# RocketometerPx_9150.net
KiCad netlist of a schematic drawn in EAGLE
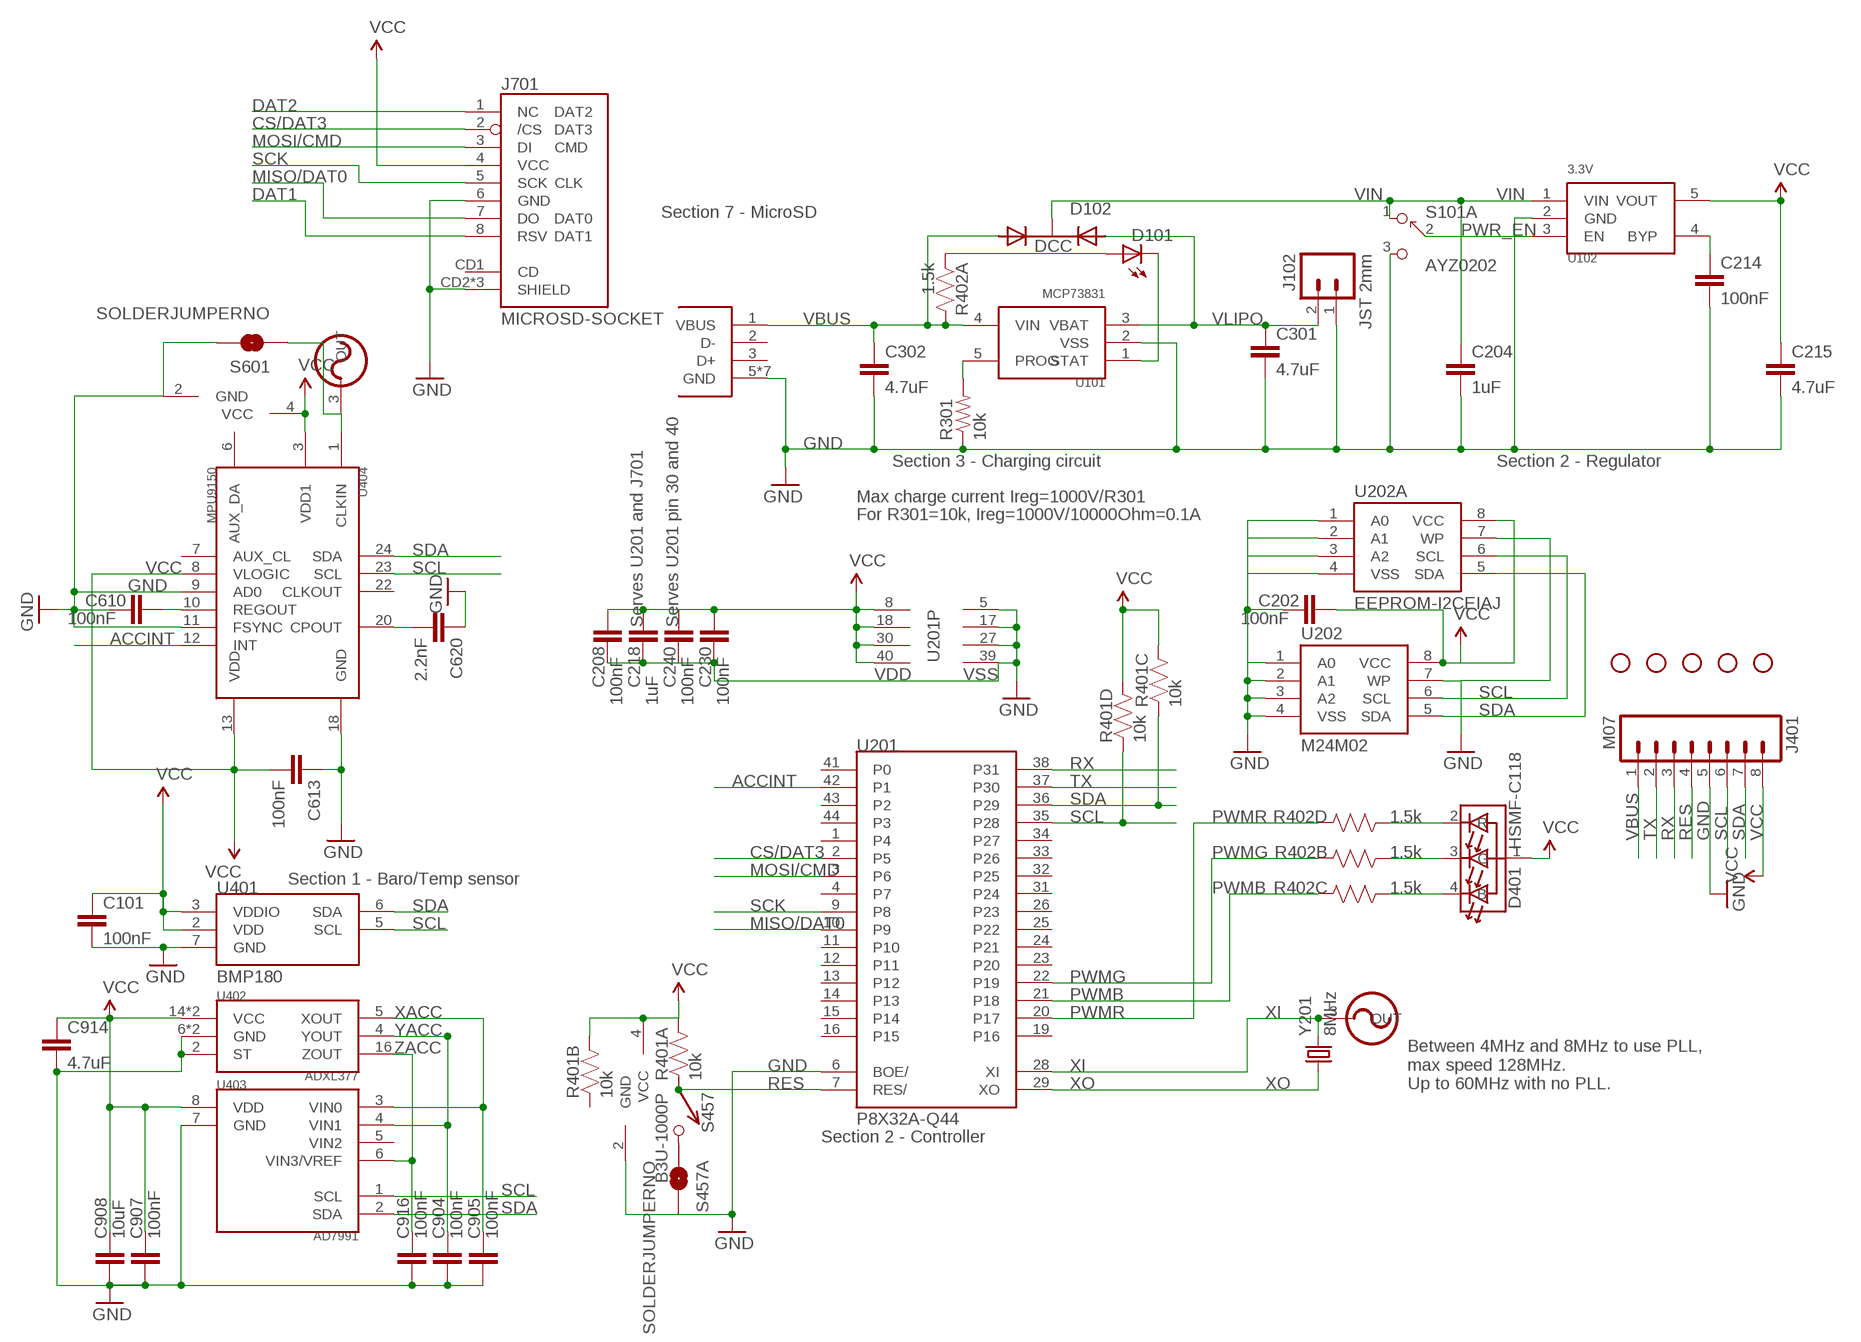
[diagram p0: schematic, sheet 1]

(export (version "E")
  (design (tool "Eeschema 10.0.6"))
  (components
    (comp (ref "C101")
      (value "100nF")
      (footprint "eagle-import:0402-CAP")
      (libsource (lib "eagle-import") (part "CAP0402-CAP"))
    )
    (comp (ref "C202")
      (value "100nF")
      (footprint "eagle-import:0402-CAP")
      (libsource (lib "eagle-import") (part "CAP0402-CAP"))
    )
    (comp (ref "C204")
      (value "1uF")
      (footprint "eagle-import:0402-CAP")
      (libsource (lib "eagle-import") (part "CAP0402-CAP"))
    )
    (comp (ref "C208")
      (value "100nF")
      (footprint "eagle-import:0402-CAP")
      (libsource (lib "eagle-import") (part "CAP0402-CAP"))
    )
    (comp (ref "C214")
      (value "100nF")
      (footprint "eagle-import:0402-CAP")
      (libsource (lib "eagle-import") (part "CAP0402-CAP"))
    )
    (comp (ref "C215")
      (value "4.7uF")
      (footprint "eagle-import:0402-CAP")
      (libsource (lib "eagle-import") (part "CAP0402-CAP"))
    )
    (comp (ref "C218")
      (value "1uF")
      (footprint "eagle-import:0402-CAP")
      (libsource (lib "eagle-import") (part "CAP0402-CAP"))
    )
    (comp (ref "C230")
      (value "100nF")
      (footprint "eagle-import:0402-CAP")
      (libsource (lib "eagle-import") (part "CAP0402-CAP"))
    )
    (comp (ref "C240")
      (value "100nF")
      (footprint "eagle-import:0402-CAP")
      (libsource (lib "eagle-import") (part "CAP0402-CAP"))
    )
    (comp (ref "C301")
      (value "4.7uF")
      (footprint "eagle-import:0402-CAP")
      (libsource (lib "eagle-import") (part "CAP0402-CAP"))
    )
    (comp (ref "C302")
      (value "4.7uF")
      (footprint "eagle-import:0402-CAP")
      (libsource (lib "eagle-import") (part "CAP0402-CAP"))
    )
    (comp (ref "C610")
      (value "100nF")
      (footprint "eagle-import:0402-CAP")
      (libsource (lib "eagle-import") (part "CAP0402-CAP"))
    )
    (comp (ref "C613")
      (value "100nF")
      (footprint "eagle-import:0402-CAP")
      (libsource (lib "eagle-import") (part "CAP0402-CAP"))
    )
    (comp (ref "C620")
      (value "2.2nF")
      (footprint "eagle-import:0402-CAP")
      (libsource (lib "eagle-import") (part "CAP0402-CAP"))
    )
    (comp (ref "C904")
      (value "100nF")
      (footprint "eagle-import:0402-CAP")
      (libsource (lib "eagle-import") (part "CAP0402-CAP"))
    )
    (comp (ref "C905")
      (value "100nF")
      (footprint "eagle-import:0402-CAP")
      (libsource (lib "eagle-import") (part "CAP0402-CAP"))
    )
    (comp (ref "C907")
      (value "100nF")
      (footprint "eagle-import:0402-CAP")
      (libsource (lib "eagle-import") (part "SparkFun-Passives_CAP0402-CAP"))
    )
    (comp (ref "C908")
      (value "10uF")
      (footprint "eagle-import:0603-CAP")
      (libsource (lib "eagle-import") (part "CAP0603-CAP"))
    )
    (comp (ref "C914")
      (value "4.7uF")
      (footprint "eagle-import:0402-CAP")
      (libsource (lib "eagle-import") (part "CAP0402-CAP"))
    )
    (comp (ref "C916")
      (value "100nF")
      (footprint "eagle-import:0402-CAP")
      (libsource (lib "eagle-import") (part "CAP0402-CAP"))
    )
    (comp (ref "D101")
      (value "YELLOW")
      (footprint "eagle-import:LED-0603")
      (libsource (lib "eagle-import") (part "LED0603"))
    )
    (comp (ref "D102")
      (value "DCC")
      (footprint "eagle-import:SOT-23-3")
      (libsource (lib "eagle-import") (part "PMEG2005CT"))
    )
    (comp (ref "D401")
      (value "HSMF-C118")
      (footprint "eagle-import:HSMF-C118")
      (libsource (lib "eagle-import") (part "HSMF-C118"))
    )
    (comp (ref "J101")
      (value "USB_MICROB_JSTGCT")
      (footprint "eagle-import:USB_MICROB_3075")
      (libsource (lib "eagle-import") (part "USB_MICROB_JSTGCT"))
    )
    (comp (ref "J102")
      (value "JST 2mm")
      (footprint "eagle-import:JST-2-SMD")
      (libsource (lib "eagle-import") (part "M02-JST-2MM-SMT"))
    )
    (comp (ref "J401")
      (value "M07")
      (footprint "eagle-import:1X08")
      (libsource (lib "eagle-import") (part "M081X08"))
    )
    (comp (ref "J701")
      (value "MICROSD-SOCKET")
      (footprint "eagle-import:MICROSD-SOCKET-PP")
      (libsource (lib "eagle-import") (part "MICROSD-SOCKET"))
    )
    (comp (ref "JP1")
      (value "STAND-OFFTIGHT")
      (footprint "eagle-import:STAND-OFF-TIGHT")
      (libsource (lib "eagle-import") (part "STAND-OFFTIGHT"))
    )
    (comp (ref "JP2")
      (value "STAND-OFFTIGHT")
      (footprint "eagle-import:STAND-OFF-TIGHT")
      (libsource (lib "eagle-import") (part "STAND-OFFTIGHT"))
    )
    (comp (ref "JP3")
      (value "STAND-OFFTIGHT")
      (footprint "eagle-import:STAND-OFF-TIGHT")
      (libsource (lib "eagle-import") (part "STAND-OFFTIGHT"))
    )
    (comp (ref "JP4")
      (value "STAND-OFFTIGHT")
      (footprint "eagle-import:STAND-OFF-TIGHT")
      (libsource (lib "eagle-import") (part "STAND-OFFTIGHT"))
    )
    (comp (ref "JP5")
      (value "STAND-OFFTIGHT")
      (footprint "eagle-import:STAND-OFF-TIGHT")
      (libsource (lib "eagle-import") (part "STAND-OFFTIGHT"))
    )
    (comp (ref "R301")
      (value "10k")
      (footprint "eagle-import:0402-RES")
      (libsource (lib "eagle-import") (part "RESISTOR0402-RES"))
    )
    (comp (ref "R401")
      (value "10k")
      (footprint "eagle-import:CRA04")
      (fields (field (name "DIGIKEY") "CRA4S810KCT-ND"))
      (libsource (lib "eagle-import") (part "RP404"))
    )
    (comp (ref "R402")
      (value "1.5k")
      (footprint "eagle-import:CRA04")
      (fields (field (name "DIGIKEY") "CRA4S81.5KCT-ND"))
      (libsource (lib "eagle-import") (part "RP404"))
    )
    (comp (ref "S101")
      (value "AYZ0202")
      (footprint "eagle-import:AYZ0202")
      (libsource (lib "eagle-import") (part "AYZ0202"))
    )
    (comp (ref "S457")
      (value "B3U-1000P")
      (footprint "eagle-import:B3U-1000P")
      (libsource (lib "eagle-import") (part "B3U-1000P"))
    )
    (comp (ref "S457A")
      (value "SOLDERJUMPERNO")
      (footprint "eagle-import:SJ_2S-NO")
      (libsource (lib "eagle-import") (part "SOLDERJUMPERNO"))
    )
    (comp (ref "S601")
      (value "SOLDERJUMPERNO")
      (footprint "eagle-import:SJ_2S-NO")
      (libsource (lib "eagle-import") (part "SOLDERJUMPERNO"))
    )
    (comp (ref "U101")
      (value "MCP73831")
      (footprint "eagle-import:SOT-23-5")
      (libsource (lib "eagle-import") (part "MCP73831"))
    )
    (comp (ref "U102")
      (value "3.3V")
      (footprint "eagle-import:SOT-23-5")
      (libsource (lib "eagle-import") (part "MIC5319D5"))
    )
    (comp (ref "U201")
      (value "P8X32A-Q44")
      (footprint "eagle-import:P8X32A-Q44")
      (fields (field (name "DIGIKEY") "P8X32A-Q44-ND"))
      (libsource (lib "eagle-import") (part "P8X32A-Q44"))
    )
    (comp (ref "U202")
      (value "M24M02")
      (footprint "eagle-import:SO8N")
      (libsource (lib "eagle-import") (part "EEPROM-I2C"))
    )
    (comp (ref "U202A")
      (value "EEPROM-I2CEIAJ")
      (footprint "eagle-import:SO08-EIAJ")
      (libsource (lib "eagle-import") (part "EEPROM-I2CEIAJ"))
    )
    (comp (ref "U401")
      (value "BMP180")
      (footprint "eagle-import:BMP180")
      (libsource (lib "eagle-import") (part "BMP180"))
    )
    (comp (ref "U402")
      (value "ADXL377")
      (footprint "eagle-import:ADXL377")
      (libsource (lib "eagle-import") (part "ADXL377"))
    )
    (comp (ref "U403")
      (value "AD7991")
      (footprint "eagle-import:SOT-23-8")
      (libsource (lib "eagle-import") (part "AD799X"))
    )
    (comp (ref "U404")
      (value "MPU9150")
      (footprint "eagle-import:MPU60X0")
      (libsource (lib "eagle-import") (part "MPU6050"))
    )
    (comp (ref "Y201")
      (value "8MHz")
      (footprint "eagle-import:CRYSTAL_SMD_3_2MM_2_5MM")
      (libsource (lib "eagle-import") (part "NX3225GD"))
    )
    (comp (ref "Y202")
      (value "8MHz")
      (footprint "eagle-import:CRYSTAL_SMD_5MM_3_2MM")
      (libsource (lib "eagle-import") (part "EM53T"))
    )
    (comp (ref "Y401")
      (value "19.2MHz")
      (footprint "eagle-import:CRYSTAL_SMD_5MM_3_2MM")
      (libsource (lib "eagle-import") (part "EM53T"))
    )
  )
  (nets
    (net (code "1") (name "/ACCINT") (class "Default")
      (node (ref "U201") (pin "42") (pinfunction "P1_42") (pintype "bidirectional"))
      (node (ref "U404") (pin "12") (pinfunction "INT_12") (pintype "output"))
    )
    (net (code "2") (name "/CS{slash}DAT3") (class "Default")
      (node (ref "J701") (pin "2") (pinfunction "/CS_2") (pintype "bidirectional"))
      (node (ref "U201") (pin "2") (pinfunction "P5_2") (pintype "bidirectional"))
    )
    (net (code "3") (name "/DAT1") (class "Default")
      (node (ref "J701") (pin "8") (pinfunction "RSV_8") (pintype "bidirectional"))
    )
    (net (code "4") (name "/DAT2") (class "Default")
      (node (ref "J701") (pin "1") (pinfunction "NC_1") (pintype "bidirectional"))
    )
    (net (code "5") (name "/MISO{slash}DAT0") (class "Default")
      (node (ref "J701") (pin "7") (pinfunction "DO_7") (pintype "bidirectional"))
      (node (ref "U201") (pin "10") (pinfunction "P9_10") (pintype "bidirectional"))
    )
    (net (code "6") (name "/MOSI{slash}CMD") (class "Default")
      (node (ref "J701") (pin "3") (pinfunction "DI_3") (pintype "bidirectional"))
      (node (ref "U201") (pin "3") (pinfunction "P6_3") (pintype "bidirectional"))
    )
    (net (code "7") (name "/PWMB") (class "Default")
      (node (ref "R402") (pin "6") (pinfunction "2_6") (pintype "passive"))
      (node (ref "U201") (pin "21") (pinfunction "P18_21") (pintype "bidirectional"))
    )
    (net (code "8") (name "/PWMG") (class "Default")
      (node (ref "R402") (pin "7") (pinfunction "2_7") (pintype "passive"))
      (node (ref "U201") (pin "22") (pinfunction "P19_22") (pintype "bidirectional"))
    )
    (net (code "9") (name "/PWMR") (class "Default")
      (node (ref "R402") (pin "5") (pinfunction "2_5") (pintype "passive"))
      (node (ref "U201") (pin "20") (pinfunction "P17_20") (pintype "bidirectional"))
    )
    (net (code "10") (name "/PWR_EN") (class "Default")
      (node (ref "S101") (pin "2") (pinfunction "P$3_2") (pintype "bidirectional"))
      (node (ref "U102") (pin "3") (pinfunction "EN_3") (pintype "bidirectional"))
    )
    (net (code "11") (name "/RES") (class "Default")
      (node (ref "J401") (pin "4") (pinfunction "4_4") (pintype "passive"))
      (node (ref "R401") (pin "1") (pinfunction "1_1") (pintype "passive"))
      (node (ref "S457") (pin "P$1") (pinfunction "1_P$1") (pintype "bidirectional"))
      (node (ref "U201") (pin "7") (pinfunction "RES/_7") (pintype "bidirectional"))
    )
    (net (code "12") (name "/RX") (class "Default")
      (node (ref "J401") (pin "3") (pinfunction "3_3") (pintype "passive"))
      (node (ref "U201") (pin "38") (pinfunction "P31_38") (pintype "bidirectional"))
    )
    (net (code "13") (name "/SCK") (class "Default")
      (node (ref "J701") (pin "5") (pinfunction "SCK_5") (pintype "bidirectional"))
      (node (ref "U201") (pin "9") (pinfunction "P8_9") (pintype "bidirectional"))
    )
    (net (code "14") (name "/SCL") (class "Default")
      (node (ref "J401") (pin "6") (pinfunction "6_6") (pintype "passive"))
      (node (ref "R401") (pin "4") (pinfunction "1_4") (pintype "passive"))
      (node (ref "U201") (pin "35") (pinfunction "P28_35") (pintype "bidirectional"))
      (node (ref "U202") (pin "6") (pinfunction "SCL_6") (pintype "bidirectional"))
      (node (ref "U202A") (pin "6") (pinfunction "SCL_6") (pintype "bidirectional"))
      (node (ref "U401") (pin "5") (pinfunction "SCL_5") (pintype "input"))
      (node (ref "U403") (pin "1") (pinfunction "SCL_1") (pintype "bidirectional"))
      (node (ref "U404") (pin "23") (pinfunction "SCL_23") (pintype "bidirectional"))
    )
    (net (code "15") (name "/SDA") (class "Default")
      (node (ref "J401") (pin "7") (pinfunction "7_7") (pintype "passive"))
      (node (ref "R401") (pin "3") (pinfunction "1_3") (pintype "passive"))
      (node (ref "U201") (pin "36") (pinfunction "P29_36") (pintype "bidirectional"))
      (node (ref "U202") (pin "5") (pinfunction "SDA_5") (pintype "bidirectional"))
      (node (ref "U202A") (pin "5") (pinfunction "SDA_5") (pintype "bidirectional"))
      (node (ref "U401") (pin "6") (pinfunction "SDA_6") (pintype "bidirectional"))
      (node (ref "U403") (pin "2") (pinfunction "SDA_2") (pintype "bidirectional"))
      (node (ref "U404") (pin "24") (pinfunction "SDA_24") (pintype "bidirectional"))
    )
    (net (code "16") (name "/TX") (class "Default")
      (node (ref "J401") (pin "2") (pinfunction "2_2") (pintype "passive"))
      (node (ref "U201") (pin "37") (pinfunction "P30_37") (pintype "bidirectional"))
    )
    (net (code "17") (name "/VBUS") (class "Default")
      (node (ref "C302") (pin "1") (pinfunction "1_1") (pintype "passive"))
      (node (ref "D102") (pin "1") (pinfunction "A1_1") (pintype "passive"))
      (node (ref "J101") (pin "1") (pinfunction "VBUS_1") (pintype "bidirectional"))
      (node (ref "J401") (pin "1") (pinfunction "1_1") (pintype "passive"))
      (node (ref "R402") (pin "8") (pinfunction "2_8") (pintype "passive"))
      (node (ref "U101") (pin "4") (pinfunction "VIN_4") (pintype "bidirectional"))
    )
    (net (code "18") (name "/VIN") (class "Default")
      (node (ref "C204") (pin "1") (pinfunction "1_1") (pintype "passive"))
      (node (ref "D102") (pin "3") (pinfunction "K_3") (pintype "passive"))
      (node (ref "S101") (pin "1") (pinfunction "P$1_1") (pintype "bidirectional"))
      (node (ref "U102") (pin "1") (pinfunction "VIN_1") (pintype "bidirectional"))
    )
    (net (code "19") (name "/VLIPO") (class "Default")
      (node (ref "C301") (pin "1") (pinfunction "1_1") (pintype "passive"))
      (node (ref "D102") (pin "2") (pinfunction "A2_2") (pintype "passive"))
      (node (ref "J102") (pin "2") (pinfunction "2_2") (pintype "passive"))
      (node (ref "U101") (pin "3") (pinfunction "VBAT_3") (pintype "bidirectional"))
    )
    (net (code "20") (name "/XACC") (class "Default")
      (node (ref "C905") (pin "1") (pinfunction "1_1") (pintype "passive"))
      (node (ref "U402") (pin "5") (pinfunction "XOUT_5") (pintype "bidirectional"))
      (node (ref "U403") (pin "3") (pinfunction "VIN0_3") (pintype "bidirectional"))
    )
    (net (code "21") (name "/XI") (class "Default")
      (node (ref "U201") (pin "28") (pinfunction "XI_28") (pintype "input"))
      (node (ref "Y201") (pin "2") (pinfunction "2_2") (pintype "passive"))
      (node (ref "Y202") (pin "3") (pinfunction "OUT_3") (pintype "bidirectional"))
    )
    (net (code "22") (name "/XO") (class "Default")
      (node (ref "U201") (pin "29") (pinfunction "XO_29") (pintype "output"))
      (node (ref "Y201") (pin "1") (pinfunction "1_1") (pintype "passive"))
    )
    (net (code "23") (name "/YACC") (class "Default")
      (node (ref "C904") (pin "1") (pinfunction "1_1") (pintype "passive"))
      (node (ref "U402") (pin "4") (pinfunction "YOUT_4") (pintype "bidirectional"))
      (node (ref "U403") (pin "4") (pinfunction "VIN1_4") (pintype "bidirectional"))
    )
    (net (code "24") (name "/ZACC") (class "Default")
      (node (ref "C916") (pin "1") (pinfunction "1_1") (pintype "passive"))
      (node (ref "U402") (pin "16") (pinfunction "ZOUT_16") (pintype "bidirectional"))
      (node (ref "U403") (pin "6") (pinfunction "VIN3/VREF_6") (pintype "bidirectional"))
    )
    (net (code "25") (name "GND") (class "Default")
      (node (ref "C101") (pin "2") (pinfunction "2_2") (pintype "passive"))
      (node (ref "C202") (pin "2") (pinfunction "2_2") (pintype "passive"))
      (node (ref "C204") (pin "2") (pinfunction "2_2") (pintype "passive"))
      (node (ref "C208") (pin "2") (pinfunction "2_2") (pintype "passive"))
      (node (ref "C214") (pin "2") (pinfunction "2_2") (pintype "passive"))
      (node (ref "C215") (pin "2") (pinfunction "2_2") (pintype "passive"))
      (node (ref "C218") (pin "2") (pinfunction "2_2") (pintype "passive"))
      (node (ref "C230") (pin "2") (pinfunction "2_2") (pintype "passive"))
      (node (ref "C240") (pin "2") (pinfunction "2_2") (pintype "passive"))
      (node (ref "C301") (pin "2") (pinfunction "2_2") (pintype "passive"))
      (node (ref "C302") (pin "2") (pinfunction "2_2") (pintype "passive"))
      (node (ref "C610") (pin "2") (pinfunction "2_2") (pintype "passive"))
      (node (ref "C613") (pin "1") (pinfunction "1_1") (pintype "passive"))
      (node (ref "C620") (pin "1") (pinfunction "1_1") (pintype "passive"))
      (node (ref "C904") (pin "2") (pinfunction "2_2") (pintype "passive"))
      (node (ref "C905") (pin "2") (pinfunction "2_2") (pintype "passive"))
      (node (ref "C907") (pin "2") (pinfunction "2_2") (pintype "passive"))
      (node (ref "C908") (pin "2") (pinfunction "2_2") (pintype "passive"))
      (node (ref "C914") (pin "2") (pinfunction "2_2") (pintype "passive"))
      (node (ref "C916") (pin "2") (pinfunction "2_2") (pintype "passive"))
      (node (ref "J101") (pin "5") (pinfunction "GND_5") (pintype "bidirectional"))
      (node (ref "J101") (pin "P$1") (pinfunction "GND_P$1") (pintype "bidirectional"))
      (node (ref "J101") (pin "P$10") (pinfunction "GND_P$10") (pintype "bidirectional"))
      (node (ref "J101") (pin "P$2") (pinfunction "GND_P$2") (pintype "bidirectional"))
      (node (ref "J101") (pin "P$3") (pinfunction "GND_P$3") (pintype "bidirectional"))
      (node (ref "J101") (pin "P$4") (pinfunction "GND_P$4") (pintype "bidirectional"))
      (node (ref "J101") (pin "P$8") (pinfunction "GND_P$8") (pintype "bidirectional"))
      (node (ref "J102") (pin "1") (pinfunction "1_1") (pintype "passive"))
      (node (ref "J401") (pin "5") (pinfunction "5_5") (pintype "passive"))
      (node (ref "J701") (pin "6") (pinfunction "GND_6") (pintype "bidirectional"))
      (node (ref "J701") (pin "CD2") (pinfunction "SHIELD_CD2") (pintype "bidirectional"))
      (node (ref "J701") (pin "GND1") (pinfunction "SHIELD_GND1") (pintype "bidirectional"))
      (node (ref "J701") (pin "GND3") (pinfunction "SHIELD_GND3") (pintype "bidirectional"))
      (node (ref "R301") (pin "1") (pinfunction "1_1") (pintype "passive"))
      (node (ref "S101") (pin "3") (pinfunction "P$2_3") (pintype "bidirectional"))
      (node (ref "S457A") (pin "2") (pinfunction "2_2") (pintype "passive"))
      (node (ref "S601") (pin "2") (pinfunction "2_2") (pintype "passive"))
      (node (ref "U101") (pin "2") (pinfunction "VSS_2") (pintype "bidirectional"))
      (node (ref "U102") (pin "2") (pinfunction "GND_2") (pintype "bidirectional"))
      (node (ref "U201") (pin "17") (pinfunction "VSS_17") (pintype "power_in"))
      (node (ref "U201") (pin "27") (pinfunction "VSS_27") (pintype "power_in"))
      (node (ref "U201") (pin "39") (pinfunction "VSS_39") (pintype "power_in"))
      (node (ref "U201") (pin "5") (pinfunction "VSS_5") (pintype "power_in"))
      (node (ref "U201") (pin "6") (pinfunction "BOE/_6") (pintype "input"))
      (node (ref "U202") (pin "1") (pinfunction "A0_1") (pintype "bidirectional"))
      (node (ref "U202") (pin "2") (pinfunction "A1_2") (pintype "bidirectional"))
      (node (ref "U202") (pin "3") (pinfunction "A2_3") (pintype "bidirectional"))
      (node (ref "U202") (pin "4") (pinfunction "VSS_4") (pintype "power_in"))
      (node (ref "U202") (pin "7") (pinfunction "WP_7") (pintype "bidirectional"))
      (node (ref "U202A") (pin "1") (pinfunction "A0_1") (pintype "bidirectional"))
      (node (ref "U202A") (pin "2") (pinfunction "A1_2") (pintype "bidirectional"))
      (node (ref "U202A") (pin "3") (pinfunction "A2_3") (pintype "bidirectional"))
      (node (ref "U202A") (pin "4") (pinfunction "VSS_4") (pintype "power_in"))
      (node (ref "U202A") (pin "7") (pinfunction "WP_7") (pintype "bidirectional"))
      (node (ref "U401") (pin "7") (pinfunction "GND_7") (pintype "power_in"))
      (node (ref "U402") (pin "2") (pinfunction "ST_2") (pintype "bidirectional"))
      (node (ref "U402") (pin "6") (pinfunction "GND_6") (pintype "bidirectional"))
      (node (ref "U402") (pin "7") (pinfunction "GND_7") (pintype "bidirectional"))
      (node (ref "U403") (pin "7") (pinfunction "GND_7") (pintype "bidirectional"))
      (node (ref "U404") (pin "11") (pinfunction "FSYNC_11") (pintype "bidirectional"))
      (node (ref "U404") (pin "18") (pinfunction "GND_18") (pintype "power_in"))
      (node (ref "U404") (pin "9") (pinfunction "AD0_9") (pintype "bidirectional"))
      (node (ref "Y202") (pin "2") (pinfunction "GND_2") (pintype "bidirectional"))
      (node (ref "Y401") (pin "2") (pinfunction "GND_2") (pintype "bidirectional"))
    )
    (net (code "26") (name "Net-(D101-PadA)") (class "Default")
      (node (ref "D101") (pin "A") (pinfunction "A_A") (pintype "passive"))
      (node (ref "R402") (pin "1") (pinfunction "1_1") (pintype "passive"))
    )
    (net (code "27") (name "Net-(D401-B)") (class "Default")
      (node (ref "D401") (pin "4") (pinfunction "B_4") (pintype "passive"))
      (node (ref "R402") (pin "3") (pinfunction "1_3") (pintype "passive"))
    )
    (net (code "28") (name "Net-(D401-G)") (class "Default")
      (node (ref "D401") (pin "3") (pinfunction "G_3") (pintype "passive"))
      (node (ref "R402") (pin "2") (pinfunction "1_2") (pintype "passive"))
    )
    (net (code "29") (name "Net-(D401-R)") (class "Default")
      (node (ref "D401") (pin "2") (pinfunction "R_2") (pintype "passive"))
      (node (ref "R402") (pin "4") (pinfunction "1_4") (pintype "passive"))
    )
    (net (code "30") (name "Net-(S457-2)") (class "Default")
      (node (ref "S457") (pin "P$2") (pinfunction "2_P$2") (pintype "bidirectional"))
      (node (ref "S457A") (pin "1") (pinfunction "1_1") (pintype "passive"))
    )
    (net (code "31") (name "Net-(U101-PROG)") (class "Default")
      (node (ref "R301") (pin "2") (pinfunction "2_2") (pintype "passive"))
      (node (ref "U101") (pin "5") (pinfunction "PROG_5") (pintype "bidirectional"))
    )
    (net (code "32") (name "Net-(U101-STAT)") (class "Default")
      (node (ref "D101") (pin "C") (pinfunction "C_C") (pintype "passive"))
      (node (ref "U101") (pin "1") (pinfunction "STAT_1") (pintype "bidirectional"))
    )
    (net (code "33") (name "Net-(U102-BYP)") (class "Default")
      (node (ref "C214") (pin "1") (pinfunction "1_1") (pintype "passive"))
      (node (ref "U102") (pin "4") (pinfunction "BYP_4") (pintype "bidirectional"))
    )
    (net (code "34") (name "Net-(U404-CLKIN)") (class "Default")
      (node (ref "S601") (pin "1") (pinfunction "1_1") (pintype "passive"))
      (node (ref "U404") (pin "1") (pinfunction "CLKIN_1") (pintype "input"))
      (node (ref "Y401") (pin "3") (pinfunction "OUT_3") (pintype "bidirectional"))
    )
    (net (code "35") (name "Net-(U404-CPOUT)") (class "Default")
      (node (ref "C620") (pin "2") (pinfunction "2_2") (pintype "passive"))
      (node (ref "U404") (pin "20") (pinfunction "CPOUT_20") (pintype "output"))
    )
    (net (code "36") (name "Net-(U404-REGOUT)") (class "Default")
      (node (ref "C610") (pin "1") (pinfunction "1_1") (pintype "passive"))
      (node (ref "U404") (pin "10") (pinfunction "REGOUT_10") (pintype "bidirectional"))
    )
    (net (code "37") (name "VCC") (class "Default")
      (node (ref "C101") (pin "1") (pinfunction "1_1") (pintype "passive"))
      (node (ref "C202") (pin "1") (pinfunction "1_1") (pintype "passive"))
      (node (ref "C208") (pin "1") (pinfunction "1_1") (pintype "passive"))
      (node (ref "C215") (pin "1") (pinfunction "1_1") (pintype "passive"))
      (node (ref "C218") (pin "1") (pinfunction "1_1") (pintype "passive"))
      (node (ref "C230") (pin "1") (pinfunction "1_1") (pintype "passive"))
      (node (ref "C240") (pin "1") (pinfunction "1_1") (pintype "passive"))
      (node (ref "C613") (pin "2") (pinfunction "2_2") (pintype "passive"))
      (node (ref "C907") (pin "1") (pinfunction "1_1") (pintype "passive"))
      (node (ref "C908") (pin "1") (pinfunction "1_1") (pintype "passive"))
      (node (ref "C914") (pin "1") (pinfunction "1_1") (pintype "passive"))
      (node (ref "D401") (pin "1") (pinfunction "A_1") (pintype "passive"))
      (node (ref "J401") (pin "8") (pinfunction "8_8") (pintype "passive"))
      (node (ref "J701") (pin "4") (pinfunction "VCC_4") (pintype "bidirectional"))
      (node (ref "R401") (pin "5") (pinfunction "2_5") (pintype "passive"))
      (node (ref "R401") (pin "6") (pinfunction "2_6") (pintype "passive"))
      (node (ref "R401") (pin "7") (pinfunction "2_7") (pintype "passive"))
      (node (ref "R401") (pin "8") (pinfunction "2_8") (pintype "passive"))
      (node (ref "U102") (pin "5") (pinfunction "VOUT_5") (pintype "bidirectional"))
      (node (ref "U201") (pin "18") (pinfunction "VDD_18") (pintype "power_in"))
      (node (ref "U201") (pin "30") (pinfunction "VDD_30") (pintype "power_in"))
      (node (ref "U201") (pin "40") (pinfunction "VDD_40") (pintype "power_in"))
      (node (ref "U201") (pin "8") (pinfunction "VDD_8") (pintype "power_in"))
      (node (ref "U202") (pin "8") (pinfunction "VCC_8") (pintype "power_in"))
      (node (ref "U202A") (pin "8") (pinfunction "VCC_8") (pintype "power_in"))
      (node (ref "U401") (pin "2") (pinfunction "VDD_2") (pintype "power_in"))
      (node (ref "U401") (pin "3") (pinfunction "VDDIO_3") (pintype "power_in"))
      (node (ref "U402") (pin "14") (pinfunction "VCC_14") (pintype "bidirectional"))
      (node (ref "U402") (pin "15") (pinfunction "VCC_15") (pintype "bidirectional"))
      (node (ref "U403") (pin "8") (pinfunction "VDD_8") (pintype "bidirectional"))
      (node (ref "U404") (pin "13") (pinfunction "VDD_13") (pintype "power_in"))
      (node (ref "U404") (pin "3") (pinfunction "VDD1_3") (pintype "input"))
      (node (ref "U404") (pin "8") (pinfunction "VLOGIC_8") (pintype "power_in"))
      (node (ref "Y202") (pin "4") (pinfunction "VCC_4") (pintype "bidirectional"))
      (node (ref "Y401") (pin "4") (pinfunction "VCC_4") (pintype "bidirectional"))
    )
    (net (code "38") (name "unconnected-(J101-D+-Pad3)") (class "Default")
      (node (ref "J101") (pin "3") (pinfunction "D+_3") (pintype "bidirectional"))
    )
    (net (code "39") (name "unconnected-(J101-D--Pad2)") (class "Default")
      (node (ref "J101") (pin "2") (pinfunction "D-_2") (pintype "bidirectional"))
    )
    (net (code "40") (name "unconnected-(J701-CD-PadCD1)") (class "Default")
      (node (ref "J701") (pin "CD1") (pinfunction "CD_CD1") (pintype "bidirectional"))
    )
    (net (code "41") (name "unconnected-(R401B-1-Pad2)") (class "Default")
      (node (ref "R401") (pin "2") (pinfunction "1_2") (pintype "passive"))
    )
    (net (code "42") (name "unconnected-(U201B-P0-Pad41)") (class "Default")
      (node (ref "U201") (pin "41") (pinfunction "P0_41") (pintype "bidirectional"))
    )
    (net (code "43") (name "unconnected-(U201B-P2-Pad43)") (class "Default")
      (node (ref "U201") (pin "43") (pinfunction "P2_43") (pintype "bidirectional"))
    )
    (net (code "44") (name "unconnected-(U201B-P3-Pad44)") (class "Default")
      (node (ref "U201") (pin "44") (pinfunction "P3_44") (pintype "bidirectional"))
    )
    (net (code "45") (name "unconnected-(U201B-P4-Pad1)") (class "Default")
      (node (ref "U201") (pin "1") (pinfunction "P4_1") (pintype "bidirectional"))
    )
    (net (code "46") (name "unconnected-(U201B-P7-Pad4)") (class "Default")
      (node (ref "U201") (pin "4") (pinfunction "P7_4") (pintype "bidirectional"))
    )
    (net (code "47") (name "unconnected-(U201B-P10-Pad11)") (class "Default")
      (node (ref "U201") (pin "11") (pinfunction "P10_11") (pintype "bidirectional"))
    )
    (net (code "48") (name "unconnected-(U201B-P11-Pad12)") (class "Default")
      (node (ref "U201") (pin "12") (pinfunction "P11_12") (pintype "bidirectional"))
    )
    (net (code "49") (name "unconnected-(U201B-P12-Pad13)") (class "Default")
      (node (ref "U201") (pin "13") (pinfunction "P12_13") (pintype "bidirectional"))
    )
    (net (code "50") (name "unconnected-(U201B-P13-Pad14)") (class "Default")
      (node (ref "U201") (pin "14") (pinfunction "P13_14") (pintype "bidirectional"))
    )
    (net (code "51") (name "unconnected-(U201B-P14-Pad15)") (class "Default")
      (node (ref "U201") (pin "15") (pinfunction "P14_15") (pintype "bidirectional"))
    )
    (net (code "52") (name "unconnected-(U201B-P15-Pad16)") (class "Default")
      (node (ref "U201") (pin "16") (pinfunction "P15_16") (pintype "bidirectional"))
    )
    (net (code "53") (name "unconnected-(U201B-P16-Pad19)") (class "Default")
      (node (ref "U201") (pin "19") (pinfunction "P16_19") (pintype "bidirectional"))
    )
    (net (code "54") (name "unconnected-(U201B-P20-Pad23)") (class "Default")
      (node (ref "U201") (pin "23") (pinfunction "P20_23") (pintype "bidirectional"))
    )
    (net (code "55") (name "unconnected-(U201B-P21-Pad24)") (class "Default")
      (node (ref "U201") (pin "24") (pinfunction "P21_24") (pintype "bidirectional"))
    )
    (net (code "56") (name "unconnected-(U201B-P22-Pad25)") (class "Default")
      (node (ref "U201") (pin "25") (pinfunction "P22_25") (pintype "bidirectional"))
    )
    (net (code "57") (name "unconnected-(U201B-P23-Pad26)") (class "Default")
      (node (ref "U201") (pin "26") (pinfunction "P23_26") (pintype "bidirectional"))
    )
    (net (code "58") (name "unconnected-(U201B-P24-Pad31)") (class "Default")
      (node (ref "U201") (pin "31") (pinfunction "P24_31") (pintype "bidirectional"))
    )
    (net (code "59") (name "unconnected-(U201B-P25-Pad32)") (class "Default")
      (node (ref "U201") (pin "32") (pinfunction "P25_32") (pintype "bidirectional"))
    )
    (net (code "60") (name "unconnected-(U201B-P26-Pad33)") (class "Default")
      (node (ref "U201") (pin "33") (pinfunction "P26_33") (pintype "bidirectional"))
    )
    (net (code "61") (name "unconnected-(U201B-P27-Pad34)") (class "Default")
      (node (ref "U201") (pin "34") (pinfunction "P27_34") (pintype "bidirectional"))
    )
    (net (code "62") (name "unconnected-(U403-VIN2-Pad5)") (class "Default")
      (node (ref "U403") (pin "5") (pinfunction "VIN2_5") (pintype "bidirectional"))
    )
    (net (code "63") (name "unconnected-(U404-AUX_CL-Pad7)") (class "Default")
      (node (ref "U404") (pin "7") (pinfunction "AUX_CL_7") (pintype "bidirectional"))
    )
    (net (code "64") (name "unconnected-(U404-AUX_DA-Pad6)") (class "Default")
      (node (ref "U404") (pin "6") (pinfunction "AUX_DA_6") (pintype "bidirectional"))
    )
    (net (code "65") (name "unconnected-(U404-CLKOUT-Pad22)") (class "Default")
      (node (ref "U404") (pin "22") (pinfunction "CLKOUT_22") (pintype "bidirectional"))
    )
  )
)
